# PCB.net
KiCad netlist of a schematic drawn in Altium Designer
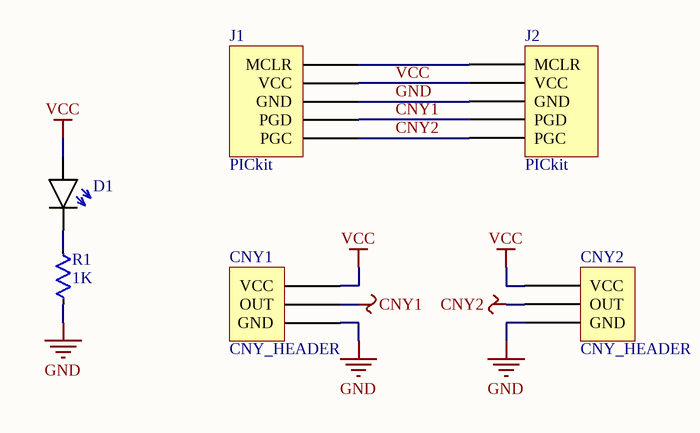
[diagram p0: PCB.SchDoc]

(export (version "E")
  (design (tool "Eeschema 10.0.6"))
  (components
    (comp (ref "CNY1")
      (value "CNY_HEADER")
      (footprint "CNY_HEADER")
      (libsource (lib "") (part "CNY_HEADER_1"))
    )
    (comp (ref "CNY2")
      (value "CNY_HEADER")
      (footprint "CNY_HEADER")
      (libsource (lib "AltiumLibraryOld") (part "CNY_HEADER"))
    )
    (comp (ref "D1") (value "LED") (footprint "LED-3MM-RED") (libsource (lib "AltiumLibrary") (part "LED")))
    (comp (ref "J1") (value "PICkit") (footprint "Header 1x5") (libsource (lib "") (part "PICkit_1")))
    (comp (ref "J2")
      (value "PICkit")
      (footprint "Header 1x5")
      (libsource (lib "AltiumLibrary") (part "PICkit"))
    )
    (comp (ref "R1")
      (value "1K")
      (footprint "RES-Axial-400mil")
      (fields (field (name "Comment") "RES"))
      (libsource (lib "AltiumLibrary") (part "RES"))
    )
  )
  (nets
    (net (code "1") (name "CNY1") (class "Default")
      (node (ref "CNY1") (pin "3") (pinfunction "OUT_3") (pintype "passive"))
      (node (ref "J1") (pin "4") (pinfunction "PGD_4") (pintype "passive"))
      (node (ref "J2") (pin "4") (pinfunction "PGD_4") (pintype "passive"))
    )
    (net (code "2") (name "CNY2") (class "Default")
      (node (ref "CNY2") (pin "3") (pinfunction "OUT_3") (pintype "passive"))
      (node (ref "J1") (pin "5") (pinfunction "PGC_5") (pintype "passive"))
      (node (ref "J2") (pin "5") (pinfunction "PGC_5") (pintype "passive"))
    )
    (net (code "3") (name "GND") (class "Default")
      (node (ref "CNY1") (pin "1") (pinfunction "GND_1") (pintype "passive"))
      (node (ref "CNY2") (pin "1") (pinfunction "GND_1") (pintype "passive"))
      (node (ref "J1") (pin "3") (pinfunction "GND_3") (pintype "power_in"))
      (node (ref "J2") (pin "3") (pinfunction "GND_3") (pintype "power_in"))
      (node (ref "R1") (pin "1") (pintype "passive"))
    )
    (net (code "4") (name "Net-(D1-PadK)") (class "Default")
      (node (ref "D1") (pin "K") (pintype "passive"))
      (node (ref "R1") (pin "2") (pintype "passive"))
    )
    (net (code "5") (name "Net-(J1-MCLR)") (class "Default")
      (node (ref "J1") (pin "1") (pinfunction "MCLR_1") (pintype "passive"))
      (node (ref "J2") (pin "1") (pinfunction "MCLR_1") (pintype "passive"))
    )
    (net (code "6") (name "VCC") (class "Default")
      (node (ref "CNY1") (pin "2") (pinfunction "VCC_2") (pintype "passive"))
      (node (ref "CNY2") (pin "2") (pinfunction "VCC_2") (pintype "passive"))
      (node (ref "D1") (pin "A") (pintype "passive"))
      (node (ref "J1") (pin "2") (pinfunction "VCC_2") (pintype "power_in"))
      (node (ref "J2") (pin "2") (pinfunction "VCC_2") (pintype "power_in"))
    )
  )
)
